# SCH_gateway.net
KiCad netlist of a schematic drawn in EasyEDA
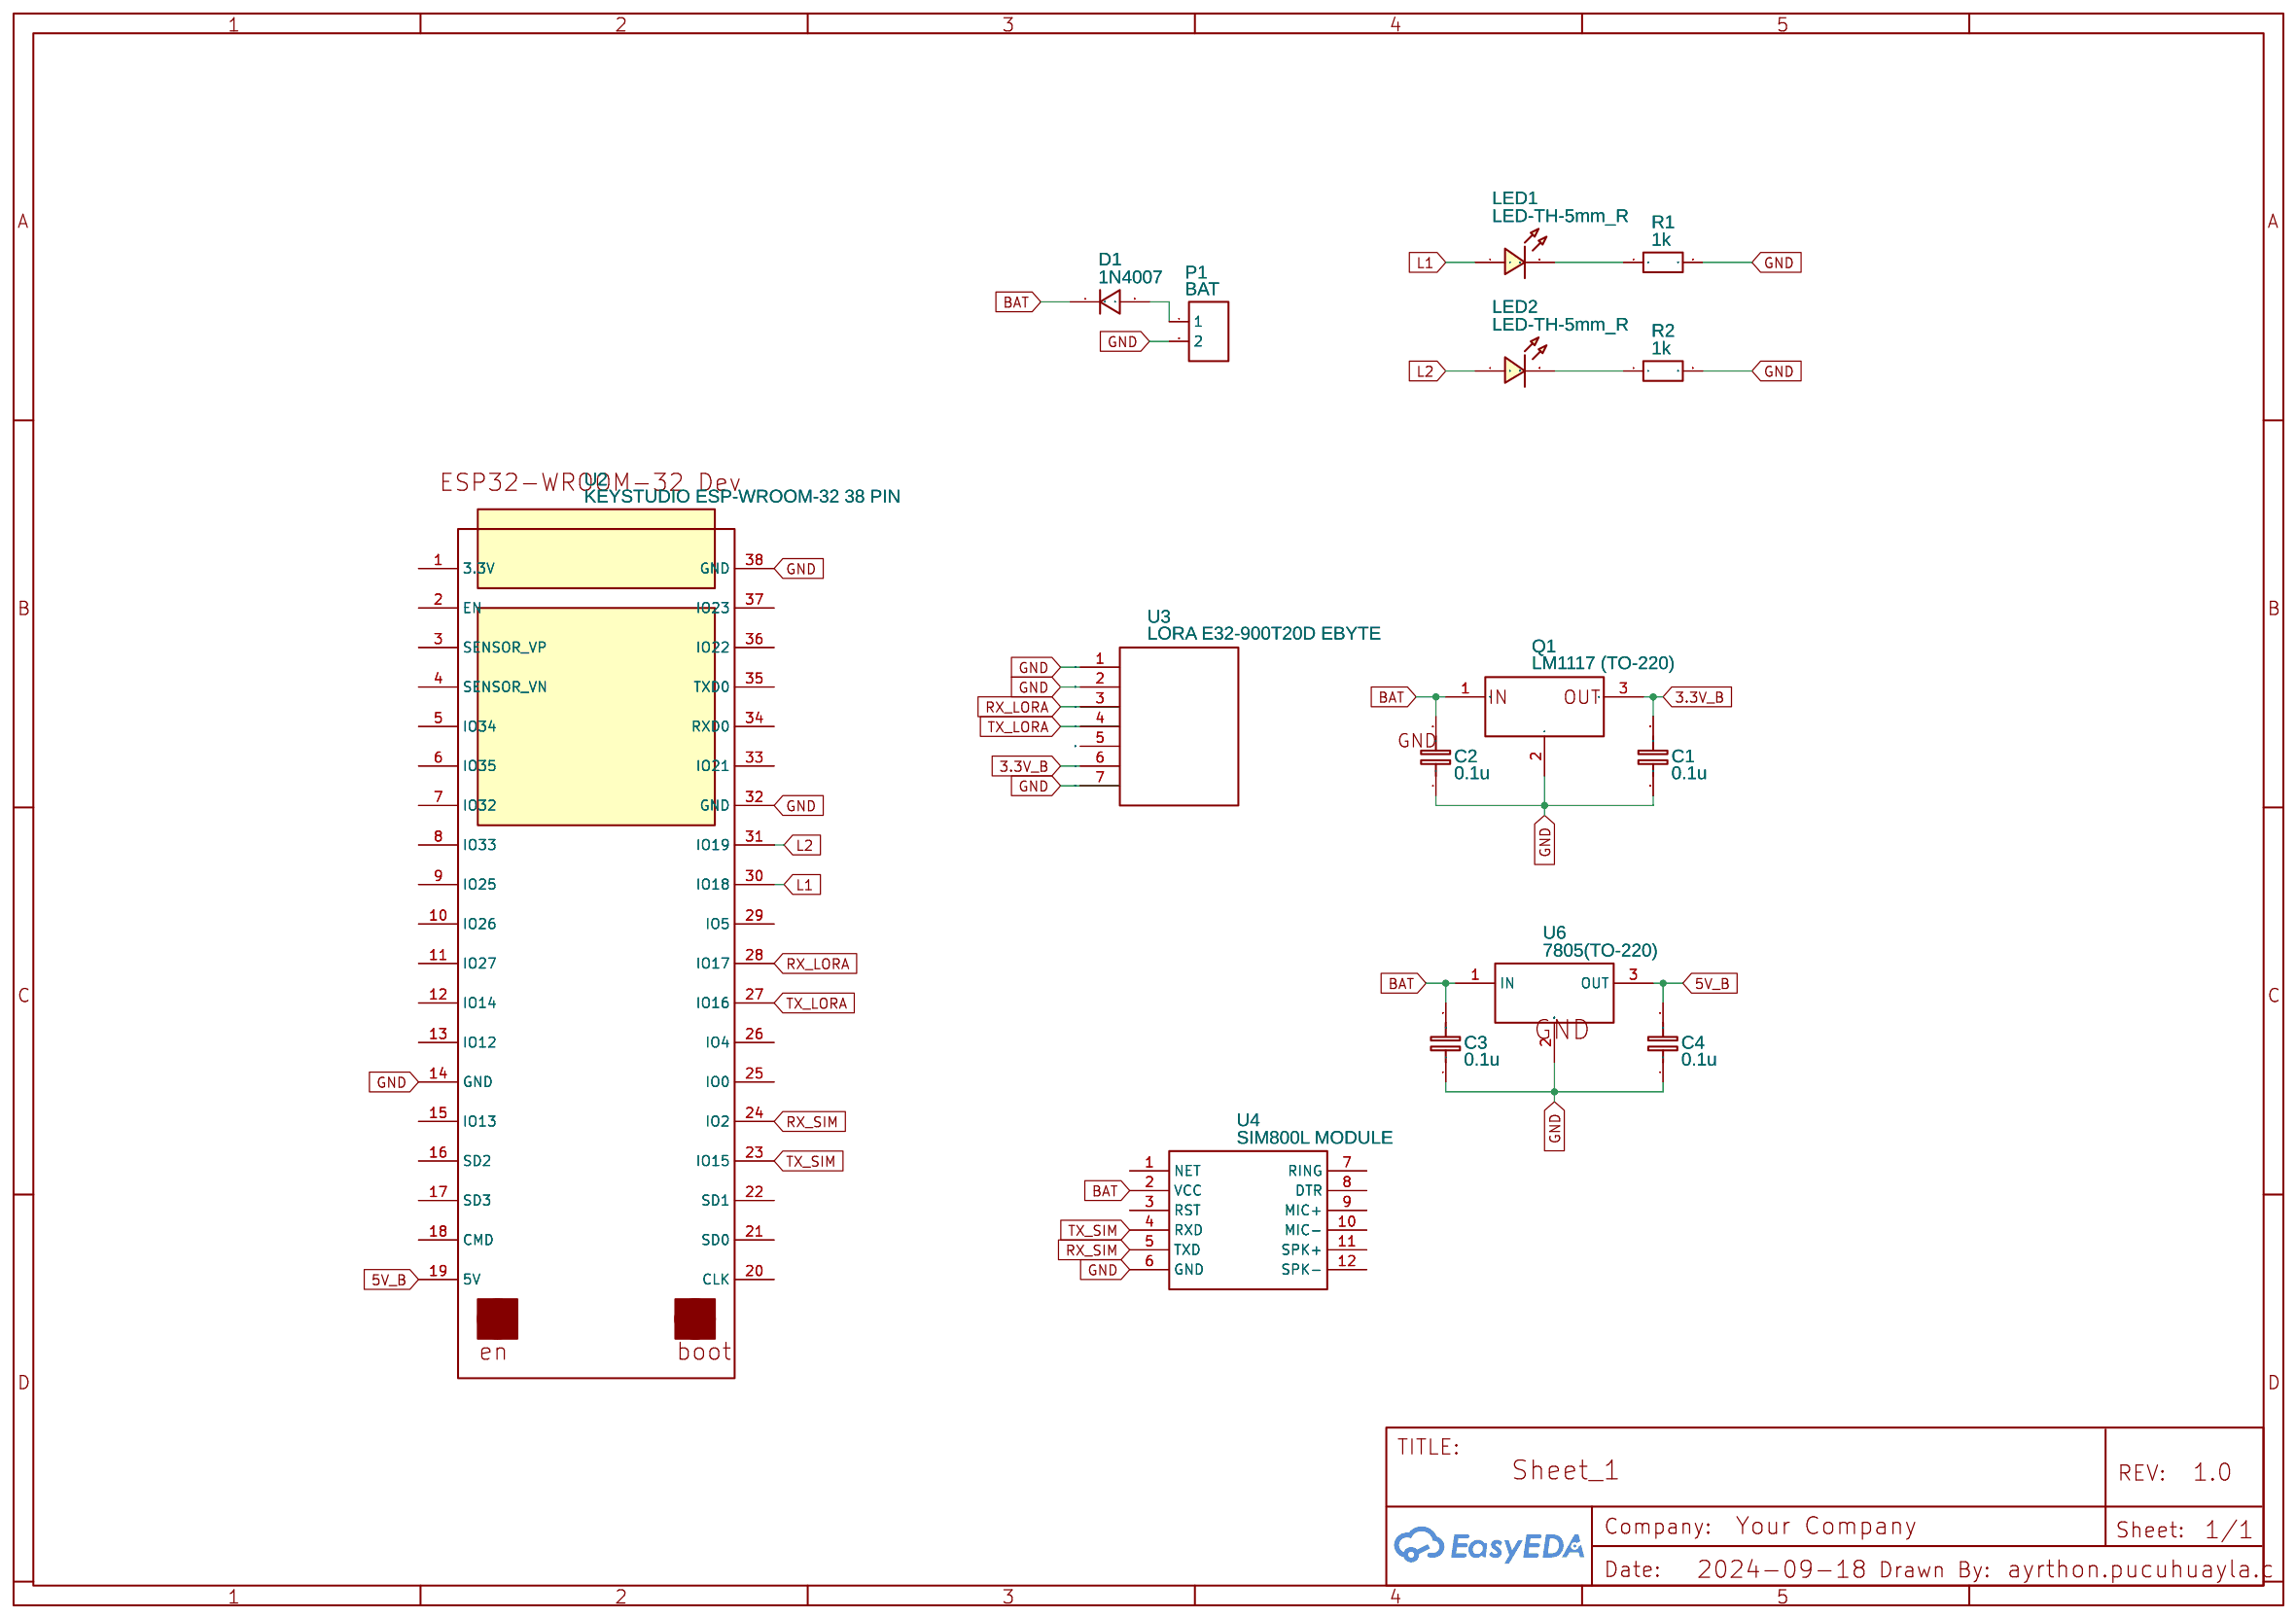
[diagram p0: schematic sheet]

(export (version "E")
  (design (tool "Eeschema 10.0.6"))
  (components
    (comp (ref "C1") (value "0.1u") (libsource (lib "") (part "C_RAD-0.1_EU")))
    (comp (ref "C2") (value "0.1u") (libsource (lib "") (part "C_RAD-0.1_EU")))
    (comp (ref "C3") (value "0.1u") (libsource (lib "") (part "C_RAD-0.1_EU")))
    (comp (ref "C4") (value "0.1u") (libsource (lib "") (part "C_RAD-0.1_EU")))
    (comp (ref "D1")
      (value "1N4007")
      (fields (field (name "Manufacturer") "SEMTECH"))
      (libsource (lib "") (part "1N4007"))
    )
    (comp (ref "LED1")
      (value "LED-TH-5mm_R")
      (fields
        (field (name "Manufacturer Part") "333-2SURD/S530-A3")
        (field (name "Manufacturer") "EVERLIGHT(台湾亿光)")
      )
      (libsource (lib "") (part "LED-TH-5mm_R"))
    )
    (comp (ref "LED2")
      (value "LED-TH-5mm_R")
      (fields
        (field (name "Manufacturer Part") "333-2SURD/S530-A3")
        (field (name "Manufacturer") "EVERLIGHT(台湾亿光)")
      )
      (libsource (lib "") (part "LED-TH-5mm_R"))
    )
    (comp (ref "P1") (value "BAT") (libsource (lib "") (part "CONN-TH_2P-P5.00")))
    (comp (ref "Q1") (value "LM1117 (TO-220)") (libsource (lib "") (part "LM1117 (TO-220)")))
    (comp (ref "R1") (value "1k") (libsource (lib "") (part "R_AXIAL-0.5_EU")))
    (comp (ref "R2") (value "1k") (libsource (lib "") (part "R_AXIAL-0.5_EU")))
    (comp (ref "U2")
      (value "KEYSTUDIO ESP-WROOM-32 38 PIN")
      (libsource (lib "") (part "KEYSTUDIO ESP-WROOM-32 38 PIN"))
    )
    (comp (ref "U3")
      (value "LORA E32-900T20D EBYTE")
      (fields (field (name "Manufacturer") "EBYTE"))
      (libsource (lib "") (part "LORA E32-900T20D EBYTE"))
    )
    (comp (ref "U4") (value "SIM800L MODULE") (libsource (lib "") (part "SIM800L MODULE")))
    (comp (ref "U6")
      (value "7805(TO-220)")
      (fields
        (field (name "Manufacturer Part") "L7805CV-DG")
        (field (name "Manufacturer") "STMicroelectronics")
      )
      (libsource (lib "") (part "7805(TO-220)"))
    )
  )
  (nets
    (net (code "1") (name "3.3V_B") (class "Default")
      (node (ref "C1") (pin "2") (pinfunction "2_2") (pintype "unspecified"))
      (node (ref "Q1") (pin "3") (pinfunction "3_3") (pintype "unspecified"))
      (node (ref "U3") (pin "6") (pinfunction "VCC_6") (pintype "unspecified"))
    )
    (net (code "2") (name "5V_B") (class "Default")
      (node (ref "C4") (pin "2") (pinfunction "2_2") (pintype "unspecified"))
      (node (ref "U2") (pin "19") (pinfunction "5V_19") (pintype "unspecified"))
      (node (ref "U6") (pin "3") (pinfunction "OUT_3") (pintype "passive"))
    )
    (net (code "3") (name "BAT") (class "Default")
      (node (ref "C2") (pin "2") (pinfunction "2_2") (pintype "unspecified"))
      (node (ref "C3") (pin "2") (pinfunction "2_2") (pintype "unspecified"))
      (node (ref "D1") (pin "1") (pinfunction "1_1") (pintype "unspecified"))
      (node (ref "Q1") (pin "1") (pinfunction "2_1") (pintype "unspecified"))
      (node (ref "U4") (pin "2") (pinfunction "VCC_2") (pintype "unspecified"))
      (node (ref "U6") (pin "1") (pinfunction "IN_1") (pintype "passive"))
    )
    (net (code "4") (name "GND") (class "Default")
      (node (ref "C1") (pin "1") (pinfunction "1_1") (pintype "unspecified"))
      (node (ref "C2") (pin "1") (pinfunction "1_1") (pintype "unspecified"))
      (node (ref "C3") (pin "1") (pinfunction "1_1") (pintype "unspecified"))
      (node (ref "C4") (pin "1") (pinfunction "1_1") (pintype "unspecified"))
      (node (ref "P1") (pin "2") (pinfunction "2_2") (pintype "unspecified"))
      (node (ref "Q1") (pin "2") (pinfunction "1_2") (pintype "unspecified"))
      (node (ref "R1") (pin "2") (pinfunction "2_2") (pintype "unspecified"))
      (node (ref "R2") (pin "2") (pinfunction "2_2") (pintype "unspecified"))
      (node (ref "U2") (pin "14") (pinfunction "GND_14") (pintype "unspecified"))
      (node (ref "U2") (pin "32") (pinfunction "GND_32") (pintype "unspecified"))
      (node (ref "U2") (pin "38") (pinfunction "GND_38") (pintype "unspecified"))
      (node (ref "U3") (pin "1") (pinfunction "M0_1") (pintype "unspecified"))
      (node (ref "U3") (pin "2") (pinfunction "M1_2") (pintype "unspecified"))
      (node (ref "U3") (pin "7") (pinfunction "GND_7") (pintype "unspecified"))
      (node (ref "U4") (pin "6") (pinfunction "GND_6") (pintype "unspecified"))
      (node (ref "U6") (pin "2") (pinfunction "GND_2") (pintype "passive"))
    )
    (net (code "5") (name "L1") (class "Default")
      (node (ref "LED1") (pin "1") (pinfunction "1_1") (pintype "unspecified"))
      (node (ref "U2") (pin "30") (pinfunction "IO18_30") (pintype "unspecified"))
    )
    (net (code "6") (name "L2") (class "Default")
      (node (ref "LED2") (pin "1") (pinfunction "1_1") (pintype "unspecified"))
      (node (ref "U2") (pin "31") (pinfunction "IO19_31") (pintype "unspecified"))
    )
    (net (code "7") (name "Net-(D1-Pad2)") (class "Default")
      (node (ref "D1") (pin "2") (pinfunction "2_2") (pintype "unspecified"))
      (node (ref "P1") (pin "1") (pinfunction "1_1") (pintype "unspecified"))
    )
    (net (code "8") (name "Net-(LED1-Pad2)") (class "Default")
      (node (ref "LED1") (pin "2") (pinfunction "2_2") (pintype "unspecified"))
      (node (ref "R1") (pin "1") (pinfunction "1_1") (pintype "unspecified"))
    )
    (net (code "9") (name "Net-(LED2-Pad2)") (class "Default")
      (node (ref "LED2") (pin "2") (pinfunction "2_2") (pintype "unspecified"))
      (node (ref "R2") (pin "1") (pinfunction "1_1") (pintype "unspecified"))
    )
    (net (code "10") (name "RX_LORA") (class "Default")
      (node (ref "U2") (pin "28") (pinfunction "IO17_28") (pintype "unspecified"))
      (node (ref "U3") (pin "3") (pinfunction "RXD_3") (pintype "unspecified"))
    )
    (net (code "11") (name "RX_SIM") (class "Default")
      (node (ref "U2") (pin "24") (pinfunction "IO2_24") (pintype "unspecified"))
      (node (ref "U4") (pin "5") (pinfunction "TXD_5") (pintype "unspecified"))
    )
    (net (code "12") (name "TX_LORA") (class "Default")
      (node (ref "U2") (pin "27") (pinfunction "IO16_27") (pintype "unspecified"))
      (node (ref "U3") (pin "4") (pinfunction "TXD_4") (pintype "unspecified"))
    )
    (net (code "13") (name "TX_SIM") (class "Default")
      (node (ref "U2") (pin "23") (pinfunction "IO15_23") (pintype "unspecified"))
      (node (ref "U4") (pin "4") (pinfunction "RXD_4") (pintype "unspecified"))
    )
    (net (code "14") (name "unconnected-(U2-3.3V-Pad1)") (class "Default")
      (node (ref "U2") (pin "1") (pinfunction "3.3V_1") (pintype "unspecified"))
    )
    (net (code "15") (name "unconnected-(U2-CLK-Pad20)") (class "Default")
      (node (ref "U2") (pin "20") (pinfunction "CLK_20") (pintype "unspecified"))
    )
    (net (code "16") (name "unconnected-(U2-CMD-Pad18)") (class "Default")
      (node (ref "U2") (pin "18") (pinfunction "CMD_18") (pintype "unspecified"))
    )
    (net (code "17") (name "unconnected-(U2-EN-Pad2)") (class "Default")
      (node (ref "U2") (pin "2") (pinfunction "EN_2") (pintype "unspecified"))
    )
    (net (code "18") (name "unconnected-(U2-IO0-Pad25)") (class "Default")
      (node (ref "U2") (pin "25") (pinfunction "IO0_25") (pintype "unspecified"))
    )
    (net (code "19") (name "unconnected-(U2-IO4-Pad26)") (class "Default")
      (node (ref "U2") (pin "26") (pinfunction "IO4_26") (pintype "unspecified"))
    )
    (net (code "20") (name "unconnected-(U2-IO5-Pad29)") (class "Default")
      (node (ref "U2") (pin "29") (pinfunction "IO5_29") (pintype "unspecified"))
    )
    (net (code "21") (name "unconnected-(U2-IO12-Pad13)") (class "Default")
      (node (ref "U2") (pin "13") (pinfunction "IO12_13") (pintype "unspecified"))
    )
    (net (code "22") (name "unconnected-(U2-IO13-Pad15)") (class "Default")
      (node (ref "U2") (pin "15") (pinfunction "IO13_15") (pintype "unspecified"))
    )
    (net (code "23") (name "unconnected-(U2-IO14-Pad12)") (class "Default")
      (node (ref "U2") (pin "12") (pinfunction "IO14_12") (pintype "unspecified"))
    )
    (net (code "24") (name "unconnected-(U2-IO21-Pad33)") (class "Default")
      (node (ref "U2") (pin "33") (pinfunction "IO21_33") (pintype "unspecified"))
    )
    (net (code "25") (name "unconnected-(U2-IO22-Pad36)") (class "Default")
      (node (ref "U2") (pin "36") (pinfunction "IO22_36") (pintype "unspecified"))
    )
    (net (code "26") (name "unconnected-(U2-IO23-Pad37)") (class "Default")
      (node (ref "U2") (pin "37") (pinfunction "IO23_37") (pintype "unspecified"))
    )
    (net (code "27") (name "unconnected-(U2-IO25-Pad9)") (class "Default")
      (node (ref "U2") (pin "9") (pinfunction "IO25_9") (pintype "unspecified"))
    )
    (net (code "28") (name "unconnected-(U2-IO26-Pad10)") (class "Default")
      (node (ref "U2") (pin "10") (pinfunction "IO26_10") (pintype "unspecified"))
    )
    (net (code "29") (name "unconnected-(U2-IO27-Pad11)") (class "Default")
      (node (ref "U2") (pin "11") (pinfunction "IO27_11") (pintype "unspecified"))
    )
    (net (code "30") (name "unconnected-(U2-IO32-Pad7)") (class "Default")
      (node (ref "U2") (pin "7") (pinfunction "IO32_7") (pintype "unspecified"))
    )
    (net (code "31") (name "unconnected-(U2-IO33-Pad8)") (class "Default")
      (node (ref "U2") (pin "8") (pinfunction "IO33_8") (pintype "unspecified"))
    )
    (net (code "32") (name "unconnected-(U2-IO34-Pad5)") (class "Default")
      (node (ref "U2") (pin "5") (pinfunction "IO34_5") (pintype "unspecified"))
    )
    (net (code "33") (name "unconnected-(U2-IO35-Pad6)") (class "Default")
      (node (ref "U2") (pin "6") (pinfunction "IO35_6") (pintype "unspecified"))
    )
    (net (code "34") (name "unconnected-(U2-RXD0-Pad34)") (class "Default")
      (node (ref "U2") (pin "34") (pinfunction "RXD0_34") (pintype "unspecified"))
    )
    (net (code "35") (name "unconnected-(U2-SD0-Pad21)") (class "Default")
      (node (ref "U2") (pin "21") (pinfunction "SD0_21") (pintype "unspecified"))
    )
    (net (code "36") (name "unconnected-(U2-SD1-Pad22)") (class "Default")
      (node (ref "U2") (pin "22") (pinfunction "SD1_22") (pintype "unspecified"))
    )
    (net (code "37") (name "unconnected-(U2-SD2-Pad16)") (class "Default")
      (node (ref "U2") (pin "16") (pinfunction "SD2_16") (pintype "unspecified"))
    )
    (net (code "38") (name "unconnected-(U2-SD3-Pad17)") (class "Default")
      (node (ref "U2") (pin "17") (pinfunction "SD3_17") (pintype "unspecified"))
    )
    (net (code "39") (name "unconnected-(U2-SENSOR_VN-Pad4)") (class "Default")
      (node (ref "U2") (pin "4") (pinfunction "SENSOR_VN_4") (pintype "unspecified"))
    )
    (net (code "40") (name "unconnected-(U2-SENSOR_VP-Pad3)") (class "Default")
      (node (ref "U2") (pin "3") (pinfunction "SENSOR_VP_3") (pintype "unspecified"))
    )
    (net (code "41") (name "unconnected-(U2-TXD0-Pad35)") (class "Default")
      (node (ref "U2") (pin "35") (pinfunction "TXD0_35") (pintype "unspecified"))
    )
    (net (code "42") (name "unconnected-(U3-AUX-Pad5)") (class "Default")
      (node (ref "U3") (pin "5") (pinfunction "AUX_5") (pintype "unspecified"))
    )
    (net (code "43") (name "unconnected-(U4-DTR-Pad8)") (class "Default")
      (node (ref "U4") (pin "8") (pinfunction "DTR_8") (pintype "unspecified"))
    )
    (net (code "44") (name "unconnected-(U4-MIC+-Pad9)") (class "Default")
      (node (ref "U4") (pin "9") (pinfunction "MIC+_9") (pintype "unspecified"))
    )
    (net (code "45") (name "unconnected-(U4-MIC--Pad10)") (class "Default")
      (node (ref "U4") (pin "10") (pinfunction "MIC-_10") (pintype "unspecified"))
    )
    (net (code "46") (name "unconnected-(U4-NET-Pad1)") (class "Default")
      (node (ref "U4") (pin "1") (pinfunction "NET_1") (pintype "unspecified"))
    )
    (net (code "47") (name "unconnected-(U4-RING-Pad7)") (class "Default")
      (node (ref "U4") (pin "7") (pinfunction "RING_7") (pintype "unspecified"))
    )
    (net (code "48") (name "unconnected-(U4-RST-Pad3)") (class "Default")
      (node (ref "U4") (pin "3") (pinfunction "RST_3") (pintype "unspecified"))
    )
    (net (code "49") (name "unconnected-(U4-SPK+-Pad11)") (class "Default")
      (node (ref "U4") (pin "11") (pinfunction "SPK+_11") (pintype "unspecified"))
    )
    (net (code "50") (name "unconnected-(U4-SPK--Pad12)") (class "Default")
      (node (ref "U4") (pin "12") (pinfunction "SPK-_12") (pintype "unspecified"))
    )
  )
)
